# Control_board.net
KiCad netlist of a schematic drawn in EAGLE
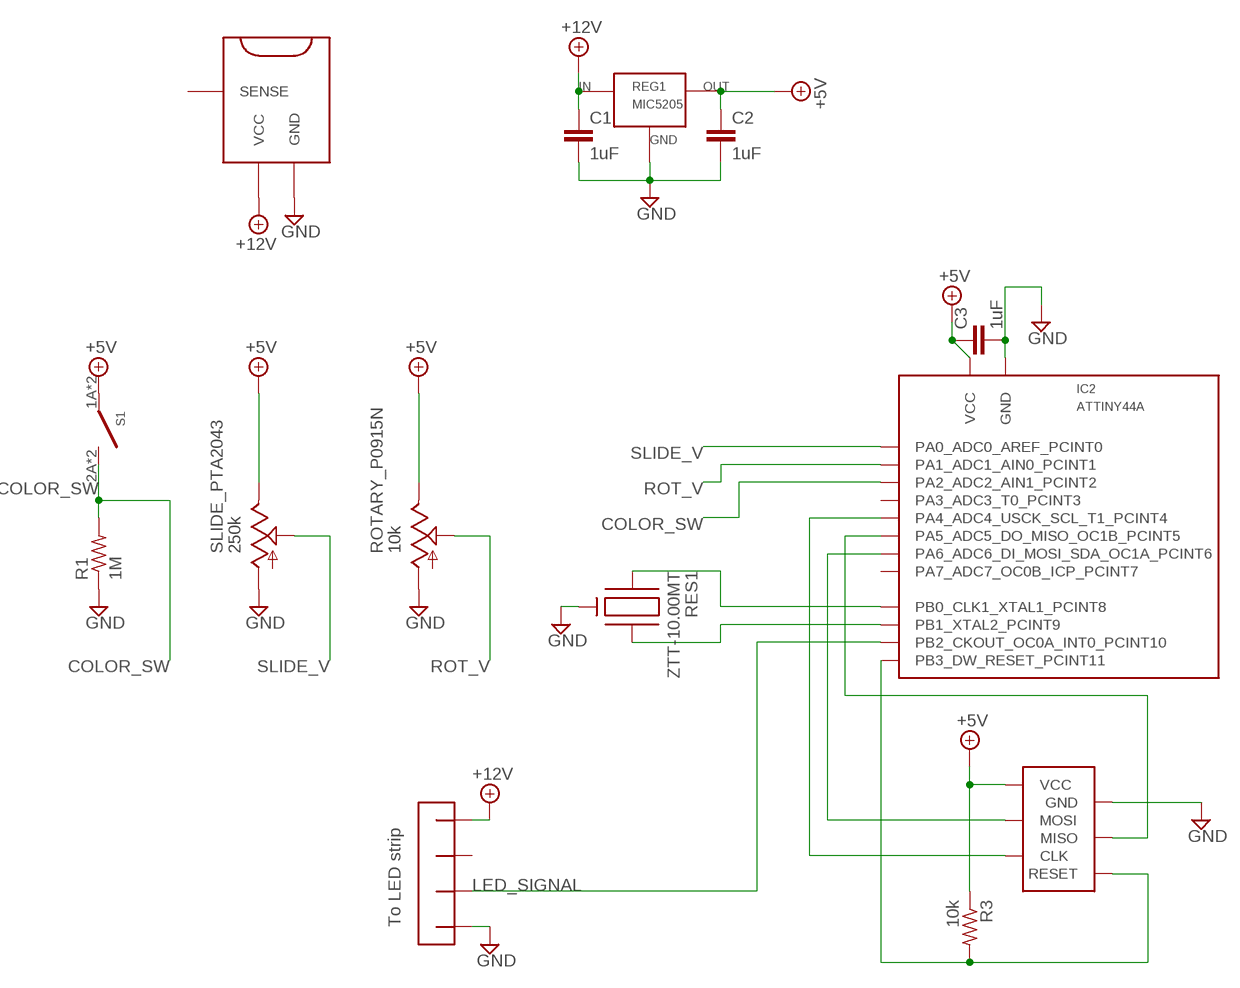
[diagram p0: schematic, sheet 1]

(export (version "E")
  (design (tool "Eeschema 10.0.6"))
  (components
    (comp (ref "C1")
      (value "1uF")
      (footprint "eagle-import:C0603")
      (libsource (lib "eagle-import") (part "C-EUC0603"))
    )
    (comp (ref "C2")
      (value "1uF")
      (footprint "eagle-import:C0603")
      (libsource (lib "eagle-import") (part "C-EUC0603"))
    )
    (comp (ref "C3")
      (value "1uF")
      (footprint "eagle-import:C0603")
      (libsource (lib "eagle-import") (part "C-EUC0603"))
    )
    (comp (ref "CONN1")
      (value "4-PIN-RIGHT-ANGLE")
      (footprint "eagle-import:S5440")
      (libsource (lib "eagle-import") (part "4-PIN-RIGHT-ANGLE"))
    )
    (comp (ref "IC2")
      (value "ATTINY44A")
      (footprint "eagle-import:QFN-20")
      (libsource (lib "eagle-import") (part "ATTINY44AQFN-20"))
    )
    (comp (ref "POW1")
      (value "PJ-202A")
      (footprint "eagle-import:PJ202A")
      (libsource (lib "eagle-import") (part "PJ-202A"))
    )
    (comp (ref "R1")
      (value "1M")
      (footprint "eagle-import:0207_7")
      (libsource (lib "eagle-import") (part "R-US_0207/7"))
    )
    (comp (ref "R3")
      (value "10k")
      (footprint "eagle-import:0207_7")
      (libsource (lib "eagle-import") (part "R-US_0207/7"))
    )
    (comp (ref "REG1")
      (value "MIC5205")
      (footprint "eagle-import:SOT-23-5")
      (libsource (lib "eagle-import") (part "MIC5205"))
    )
    (comp (ref "RES1")
      (value "ZTT-10.00MT")
      (footprint "eagle-import:3-PIN-THROUGH-HOLE")
      (libsource (lib "eagle-import") (part "ZTT-16.00MX"))
    )
    (comp (ref "ROTARY_P0915N")
      (value "10k")
      (footprint "eagle-import:P0915N")
      (libsource (lib "eagle-import") (part "P0915N"))
    )
    (comp (ref "S1")
      (value "D6R00")
      (footprint "eagle-import:D6R00")
      (libsource (lib "eagle-import") (part "D6R00"))
    )
    (comp (ref "SLIDE_PTA2043")
      (value "250k")
      (footprint "eagle-import:PTA2043")
      (libsource (lib "eagle-import") (part "PTA2043"))
    )
    (comp (ref "U$1")
      (value "ISP")
      (footprint "eagle-import:ISP")
      (libsource (lib "eagle-import") (part "ISP"))
    )
  )
  (nets
    (net (code "1") (name "+5V") (class "Default")
      (node (ref "C2") (pin "1") (pinfunction "1_1") (pintype "passive"))
      (node (ref "C3") (pin "1") (pinfunction "1_1") (pintype "passive"))
      (node (ref "IC2") (pin "P$9") (pinfunction "VCC_P$9") (pintype "bidirectional"))
      (node (ref "R3") (pin "1") (pinfunction "1_1") (pintype "passive"))
      (node (ref "REG1") (pin "5") (pinfunction "OUT_5") (pintype "bidirectional"))
      (node (ref "ROTARY_P0915N") (pin "R13") (pinfunction "B_R13") (pintype "passive"))
      (node (ref "S1") (pin "1A") (pinfunction "P$1_1A") (pintype "passive"))
      (node (ref "S1") (pin "1B") (pinfunction "P$1_1B") (pintype "passive"))
      (node (ref "SLIDE_PTA2043") (pin "P3") (pinfunction "B_P3") (pintype "passive"))
      (node (ref "U$1") (pin "VCC") (pinfunction "VCC_VCC") (pintype "bidirectional"))
    )
    (net (code "2") (name "+12V") (class "Default")
      (node (ref "C1") (pin "1") (pinfunction "1_1") (pintype "passive"))
      (node (ref "CONN1") (pin "P$4") (pinfunction "P$4_P$4") (pintype "bidirectional"))
      (node (ref "POW1") (pin "1") (pinfunction "VCC_1") (pintype "power_in"))
      (node (ref "REG1") (pin "1") (pinfunction "IN_1") (pintype "bidirectional"))
      (node (ref "REG1") (pin "3") (pinfunction "IN_3") (pintype "bidirectional"))
    )
    (net (code "3") (name "/COLOR_SW") (class "Default")
      (node (ref "IC2") (pin "P$3") (pinfunction "PA2_ADC2_AIN1_PCINT2_P$3") (pintype "bidirectional"))
      (node (ref "R1") (pin "2") (pinfunction "2_2") (pintype "passive"))
      (node (ref "S1") (pin "2A") (pinfunction "P$2_2A") (pintype "passive"))
      (node (ref "S1") (pin "2B") (pinfunction "P$2_2B") (pintype "passive"))
    )
    (net (code "4") (name "/LED_SIGNAL") (class "Default")
      (node (ref "CONN1") (pin "P$2") (pinfunction "P$2_P$2") (pintype "bidirectional"))
      (node (ref "IC2") (pin "P$14") (pinfunction "PB2_CKOUT_OC0A_INT0_PCINT10_P$14") (pintype "bidirectional"))
    )
    (net (code "5") (name "/ROT_V") (class "Default")
      (node (ref "IC2") (pin "P$4") (pinfunction "PA1_ADC1_AIN0_PCINT1_P$4") (pintype "bidirectional"))
      (node (ref "ROTARY_P0915N") (pin "R12") (pinfunction "S_R12") (pintype "passive"))
    )
    (net (code "6") (name "/SLIDE_V") (class "Default")
      (node (ref "IC2") (pin "P$5") (pinfunction "PA0_ADC0_AREF_PCINT0_P$5") (pintype "bidirectional"))
      (node (ref "SLIDE_PTA2043") (pin "P2") (pinfunction "S_P2") (pintype "passive"))
    )
    (net (code "7") (name "GND") (class "Default")
      (node (ref "C1") (pin "2") (pinfunction "2_2") (pintype "passive"))
      (node (ref "C2") (pin "2") (pinfunction "2_2") (pintype "passive"))
      (node (ref "C3") (pin "2") (pinfunction "2_2") (pintype "passive"))
      (node (ref "CONN1") (pin "P$1") (pinfunction "P$1_P$1") (pintype "bidirectional"))
      (node (ref "IC2") (pin "P$8") (pinfunction "GND_P$8") (pintype "bidirectional"))
      (node (ref "IC2") (pin "PAD") (pinfunction "GND_PAD") (pintype "bidirectional"))
      (node (ref "POW1") (pin "2") (pinfunction "GND_2") (pintype "power_in"))
      (node (ref "R1") (pin "1") (pinfunction "1_1") (pintype "passive"))
      (node (ref "REG1") (pin "2") (pinfunction "GND_2") (pintype "bidirectional"))
      (node (ref "RES1") (pin "2") (pinfunction "GND_2") (pintype "bidirectional"))
      (node (ref "ROTARY_P0915N") (pin "R11") (pinfunction "A_R11") (pintype "passive"))
      (node (ref "SLIDE_PTA2043") (pin "P1") (pinfunction "A_P1") (pintype "passive"))
      (node (ref "U$1") (pin "GND") (pinfunction "GND_GND") (pintype "bidirectional"))
    )
    (net (code "8") (name "Net-(IC2-PA4_ADC4_USCK_SCL_T1_PCINT4)") (class "Default")
      (node (ref "IC2") (pin "P$1") (pinfunction "PA4_ADC4_USCK_SCL_T1_PCINT4_P$1") (pintype "bidirectional"))
      (node (ref "U$1") (pin "SCK") (pinfunction "CLK_SCK") (pintype "bidirectional"))
    )
    (net (code "9") (name "Net-(IC2-PA5_ADC5_DO_MISO_OC1B_PCINT5)") (class "Default")
      (node (ref "IC2") (pin "P$20") (pinfunction "PA5_ADC5_DO_MISO_OC1B_PCINT5_P$20") (pintype "bidirectional"))
      (node (ref "U$1") (pin "MISO") (pinfunction "MISO_MISO") (pintype "bidirectional"))
    )
    (net (code "10") (name "Net-(IC2-PA6_ADC6_DI_MOSI_SDA_OC1A_PCINT6)") (class "Default")
      (node (ref "IC2") (pin "P$16") (pinfunction "PA6_ADC6_DI_MOSI_SDA_OC1A_PCINT6_P$16") (pintype "bidirectional"))
      (node (ref "U$1") (pin "MOSI") (pinfunction "MOSI_MOSI") (pintype "bidirectional"))
    )
    (net (code "11") (name "Net-(IC2-PB0_CLK1_XTAL1_PCINT8)") (class "Default")
      (node (ref "IC2") (pin "P$11") (pinfunction "PB0_CLK1_XTAL1_PCINT8_P$11") (pintype "bidirectional"))
      (node (ref "RES1") (pin "1") (pinfunction "X1_1") (pintype "bidirectional"))
    )
    (net (code "12") (name "Net-(IC2-PB1_XTAL2_PCINT9)") (class "Default")
      (node (ref "IC2") (pin "P$12") (pinfunction "PB1_XTAL2_PCINT9_P$12") (pintype "bidirectional"))
      (node (ref "RES1") (pin "3") (pinfunction "X2_3") (pintype "bidirectional"))
    )
    (net (code "13") (name "Net-(IC2-PB3_DW_RESET_PCINT11)") (class "Default")
      (node (ref "IC2") (pin "P$13") (pinfunction "PB3_DW_RESET_PCINT11_P$13") (pintype "bidirectional"))
      (node (ref "R3") (pin "2") (pinfunction "2_2") (pintype "passive"))
      (node (ref "U$1") (pin "RESET") (pinfunction "RESET_RESET") (pintype "bidirectional"))
    )
    (net (code "14") (name "unconnected-(CONN1-PadP$3)") (class "Default")
      (node (ref "CONN1") (pin "P$3") (pinfunction "P$3_P$3") (pintype "bidirectional"))
    )
    (net (code "15") (name "unconnected-(IC2-PA3_ADC3_T0_PCINT3-PadP$2)") (class "Default")
      (node (ref "IC2") (pin "P$2") (pinfunction "PA3_ADC3_T0_PCINT3_P$2") (pintype "bidirectional"))
    )
    (net (code "16") (name "unconnected-(IC2-PA7_ADC7_OC0B_ICP_PCINT7-PadP$15)") (class "Default")
      (node (ref "IC2") (pin "P$15") (pinfunction "PA7_ADC7_OC0B_ICP_PCINT7_P$15") (pintype "bidirectional"))
    )
    (net (code "17") (name "unconnected-(POW1-SENSE-Pad3)") (class "Default")
      (node (ref "POW1") (pin "3") (pinfunction "SENSE_3") (pintype "bidirectional"))
    )
  )
)
